# Lamp_Logic_Board_10.net
KiCad netlist of a schematic drawn in EAGLE
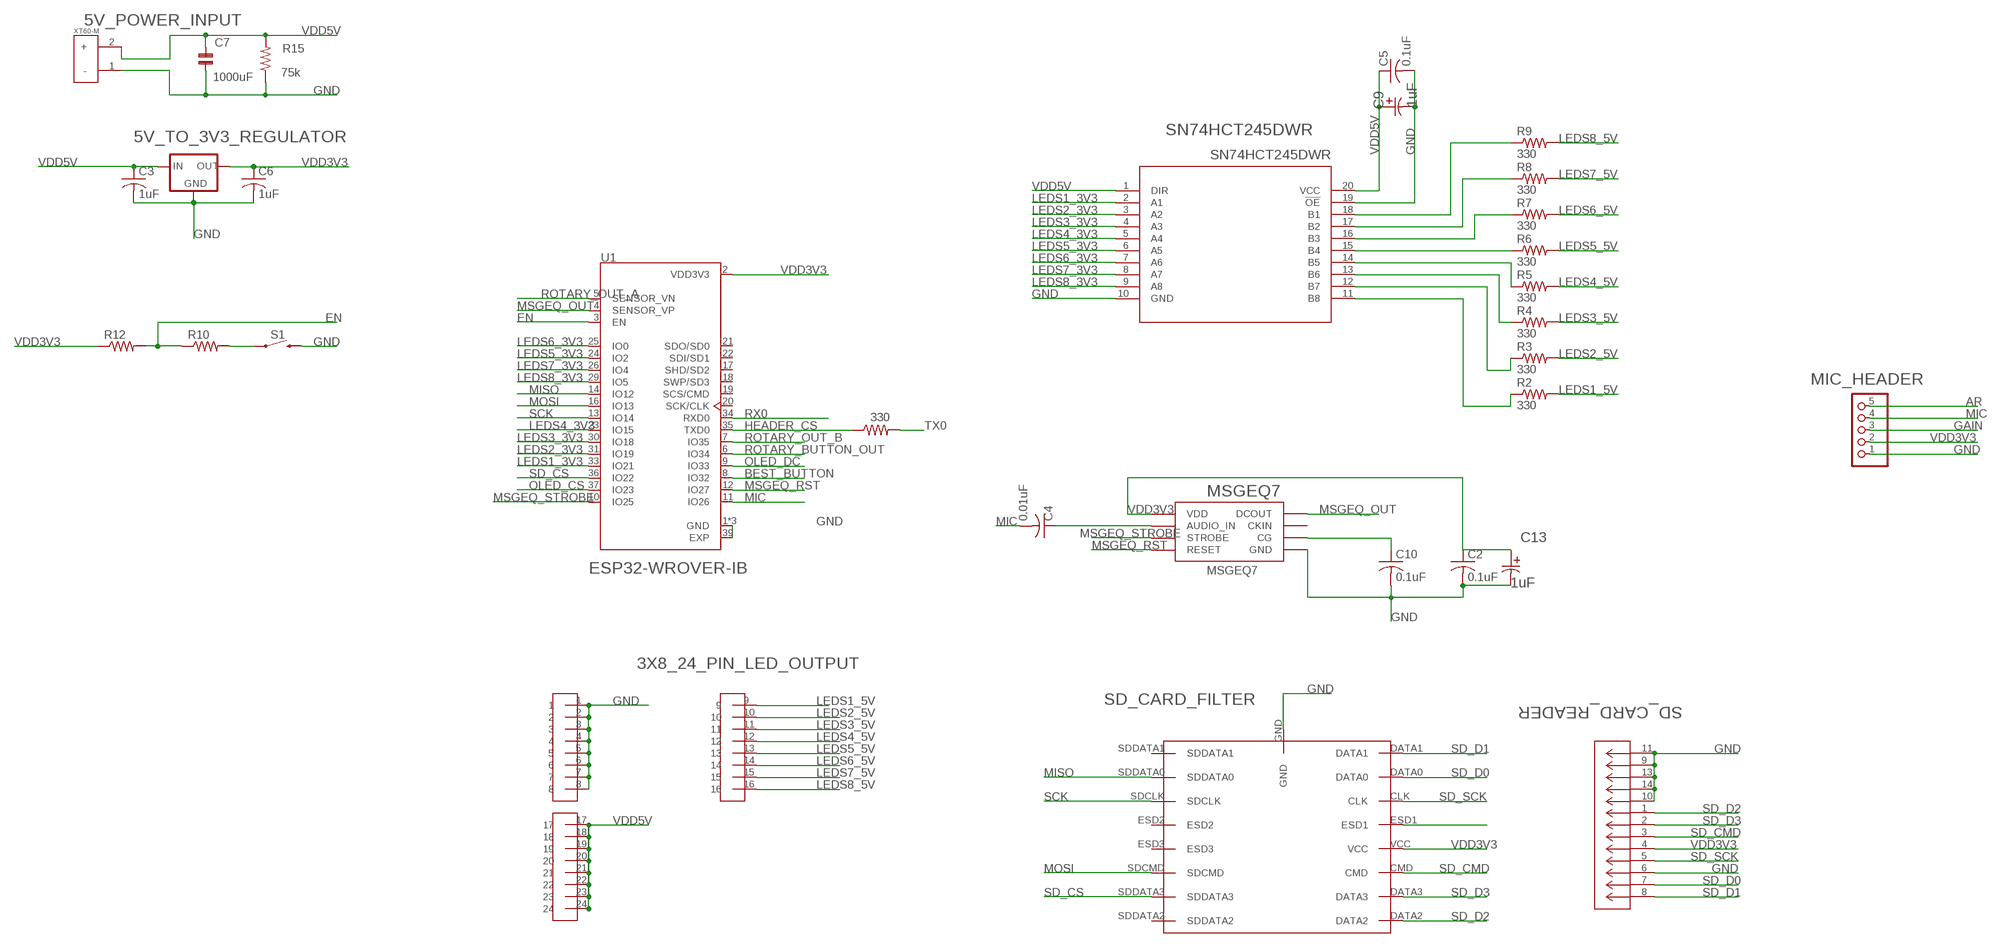
[diagram p0: schematic, sheet 1]

(export (version "E")
  (design (tool "Eeschema 10.0.6"))
  (components
    (comp (ref "3X8_24_PIN_LED_OUTPUT")
      (value "3X8PINHEAD")
      (footprint "eagle-import:3X8PINHEAD")
      (libsource (lib "eagle-import") (part "3X8PINHEAD"))
    )
    (comp (ref "5V_POWER_INPUT")
      (value "XT60-M")
      (footprint "eagle-import:AMASS_XT60-M")
      (fields (field (name "MF") "AMASS"))
      (libsource (lib "eagle-import") (part "XT60-M"))
    )
    (comp (ref "5V_TO_3V3_REGULATOR")
      (value "LM1117MP-1.8")
      (footprint "eagle-import:SOT223")
      (fields (field (name "MF") "Texas Instruments"))
      (libsource (lib "eagle-import") (part "LM1117?-MP1.8"))
    )
    (comp (ref "C2")
      (value "0.1uF")
      (footprint "eagle-import:C0805")
      (libsource (lib "eagle-import") (part "C-USC0805"))
    )
    (comp (ref "C3")
      (value "1uF")
      (footprint "eagle-import:C0402")
      (libsource (lib "eagle-import") (part "C-USC0402"))
    )
    (comp (ref "C4")
      (value "0.01uF")
      (footprint "eagle-import:C0402")
      (libsource (lib "eagle-import") (part "C-USC0402"))
    )
    (comp (ref "C5")
      (value "0.1uF")
      (footprint "eagle-import:C0805")
      (libsource (lib "eagle-import") (part "C-USC0805"))
    )
    (comp (ref "C6")
      (value "1uF")
      (footprint "eagle-import:C0402")
      (libsource (lib "eagle-import") (part "C-USC0402"))
    )
    (comp (ref "C7")
      (value "1000uF")
      (footprint "eagle-import:ENP2,0-5")
      (libsource (lib "eagle-import") (part "C-BP-2,0X5"))
    )
    (comp (ref "C9")
      (value "1uF")
      (footprint "eagle-import:CAP_EEFC_B")
      (fields (field (name "MANUFACTURER_PART_NUMBER") "EEEFC1V1R0R"))
      (libsource (lib "eagle-import") (part "EEEFC1V1R0R"))
    )
    (comp (ref "C10")
      (value "0.1uF")
      (footprint "eagle-import:C0805")
      (libsource (lib "eagle-import") (part "C-USC0805"))
    )
    (comp (ref "C13")
      (value "1uF")
      (footprint "eagle-import:CAP_EEFC_B")
      (fields (field (name "MANUFACTURER_PART_NUMBER") "EEEFC1V1R0R"))
      (libsource (lib "eagle-import") (part "EEEFC1V1R0R"))
    )
    (comp (ref "MIC_HEADER")
      (value "PINHD-1X5")
      (footprint "eagle-import:1X05")
      (libsource (lib "eagle-import") (part "PINHD-1X5"))
    )
    (comp (ref "MSGEQ7")
      (value "MSGEQ7DIL")
      (footprint "eagle-import:DIL-08")
      (fields
        (field (name "DIGI-KEY_PART_NUMBER") "1568-1544-ND")
        (field (name "MF") "SparkFun Electronics")
        (field (name "MP") "MSGEQ7")
      )
      (libsource (lib "eagle-import") (part "MSGEQ7DIL"))
    )
    (comp (ref "R1")
      (value "330")
      (footprint "eagle-import:R1206")
      (libsource (lib "eagle-import") (part "R-US_R1206"))
    )
    (comp (ref "R2")
      (value "330")
      (footprint "eagle-import:R1206")
      (libsource (lib "eagle-import") (part "R-US_R1206"))
    )
    (comp (ref "R3")
      (value "330")
      (footprint "eagle-import:R1206")
      (libsource (lib "eagle-import") (part "R-US_R1206"))
    )
    (comp (ref "R4")
      (value "330")
      (footprint "eagle-import:R1206")
      (libsource (lib "eagle-import") (part "R-US_R1206"))
    )
    (comp (ref "R5")
      (value "330")
      (footprint "eagle-import:R1206")
      (libsource (lib "eagle-import") (part "R-US_R1206"))
    )
    (comp (ref "R6")
      (value "330")
      (footprint "eagle-import:R1206")
      (libsource (lib "eagle-import") (part "R-US_R1206"))
    )
    (comp (ref "R7")
      (value "330")
      (footprint "eagle-import:R1206")
      (libsource (lib "eagle-import") (part "R-US_R1206"))
    )
    (comp (ref "R8")
      (value "330")
      (footprint "eagle-import:R1206")
      (libsource (lib "eagle-import") (part "R-US_R1206"))
    )
    (comp (ref "R9")
      (value "330")
      (footprint "eagle-import:R1206")
      (libsource (lib "eagle-import") (part "R-US_R1206"))
    )
    (comp (ref "R10")
      (value "330")
      (footprint "eagle-import:R1206")
      (libsource (lib "eagle-import") (part "R-US_R1206"))
    )
    (comp (ref "R12")
      (value "12k")
      (footprint "eagle-import:R0603")
      (libsource (lib "eagle-import") (part "R-US_R0603"))
    )
    (comp (ref "R15")
      (value "75k")
      (footprint "eagle-import:0309_12")
      (libsource (lib "eagle-import") (part "R-US_0309/12"))
    )
    (comp (ref "S1")
      (value "MOMENTARY-SWITCH-SPST-SMD-6.0X3.5MM")
      (footprint "eagle-import:TACTILE_SWITCH_SMD_6.0X3.5MM")
      (libsource (lib "eagle-import") (part "MOMENTARY-SWITCH-SPST-SMD-6.0X3.5MM"))
    )
    (comp (ref "SD_CARD_FILTER")
      (value "CM1624-08DE")
      (footprint "eagle-import:CM1624-08DE")
      (libsource (lib "eagle-import") (part "CM1624-08DE"))
    )
    (comp (ref "SD_CARD_READER")
      (value "LLC")
      (footprint "eagle-import:CON00218_8")
      (libsource (lib "eagle-import") (part "LLC"))
    )
    (comp (ref "SN74HCT245DWR")
      (value "SN74HCT245DWR")
      (footprint "eagle-import:DW20")
      (libsource (lib "eagle-import") (part "SN74HCT245DWR"))
    )
    (comp (ref "U1")
      (value "ESP32-WROVER-IB")
      (footprint "eagle-import:XCVR_ESP32-WROVER-I")
      (fields (field (name "MF") "Espressif Systems") (field (name "MP") "ESP32-WROVER-I"))
      (libsource (lib "eagle-import") (part "ESP32-WROVER-I"))
    )
  )
  (nets
    (net (code "1") (name "AR") (class "Default")
      (node (ref "MIC_HEADER") (pin "5") (pinfunction "5_5") (pintype "passive"))
    )
    (net (code "2") (name "BEST_BUTTON") (class "Default")
      (node (ref "U1") (pin "8") (pinfunction "IO32_8") (pintype "bidirectional"))
    )
    (net (code "3") (name "EN") (class "Default")
      (node (ref "R10") (pin "1") (pinfunction "1_1") (pintype "passive"))
      (node (ref "R12") (pin "2") (pinfunction "2_2") (pintype "passive"))
      (node (ref "U1") (pin "3") (pinfunction "EN_3") (pintype "input"))
    )
    (net (code "4") (name "GAIN") (class "Default")
      (node (ref "MIC_HEADER") (pin "3") (pinfunction "3_3") (pintype "passive"))
    )
    (net (code "5") (name "GND") (class "Default")
      (node (ref "3X8_24_PIN_LED_OUTPUT") (pin "1") (pinfunction "1_1") (pintype "bidirectional"))
      (node (ref "3X8_24_PIN_LED_OUTPUT") (pin "2") (pinfunction "2_2") (pintype "bidirectional"))
      (node (ref "3X8_24_PIN_LED_OUTPUT") (pin "3") (pinfunction "3_3") (pintype "bidirectional"))
      (node (ref "3X8_24_PIN_LED_OUTPUT") (pin "4") (pinfunction "4_4") (pintype "bidirectional"))
      (node (ref "3X8_24_PIN_LED_OUTPUT") (pin "5") (pinfunction "5_5") (pintype "bidirectional"))
      (node (ref "3X8_24_PIN_LED_OUTPUT") (pin "6") (pinfunction "6_6") (pintype "bidirectional"))
      (node (ref "3X8_24_PIN_LED_OUTPUT") (pin "7") (pinfunction "7_7") (pintype "bidirectional"))
      (node (ref "3X8_24_PIN_LED_OUTPUT") (pin "8") (pinfunction "8_8") (pintype "bidirectional"))
      (node (ref "5V_POWER_INPUT") (pin "1") (pinfunction "-_1") (pintype "passive"))
      (node (ref "5V_TO_3V3_REGULATOR") (pin "1") (pinfunction "GND_1") (pintype "input"))
      (node (ref "C10") (pin "2") (pinfunction "2_2") (pintype "passive"))
      (node (ref "C13") (pin "2") (pinfunction "2_2") (pintype "passive"))
      (node (ref "C2") (pin "2") (pinfunction "2_2") (pintype "passive"))
      (node (ref "C3") (pin "2") (pinfunction "2_2") (pintype "passive"))
      (node (ref "C5") (pin "2") (pinfunction "2_2") (pintype "passive"))
      (node (ref "C6") (pin "2") (pinfunction "2_2") (pintype "passive"))
      (node (ref "C7") (pin "1") (pinfunction "1_1") (pintype "passive"))
      (node (ref "C9") (pin "2") (pinfunction "2_2") (pintype "passive"))
      (node (ref "MIC_HEADER") (pin "1") (pinfunction "1_1") (pintype "passive"))
      (node (ref "MSGEQ7") (pin "2") (pinfunction "GND_2") (pintype "bidirectional"))
      (node (ref "R15") (pin "1") (pinfunction "1_1") (pintype "passive"))
      (node (ref "S1") (pin "2") (pinfunction "2_2") (pintype "passive"))
      (node (ref "SD_CARD_FILTER") (pin "GND") (pinfunction "GND_GND") (pintype "bidirectional"))
      (node (ref "SD_CARD_READER") (pin "10") (pinfunction "10_10") (pintype "passive"))
      (node (ref "SD_CARD_READER") (pin "11") (pinfunction "11_11") (pintype "passive"))
      (node (ref "SD_CARD_READER") (pin "13") (pinfunction "13_13") (pintype "passive"))
      (node (ref "SD_CARD_READER") (pin "14") (pinfunction "14_14") (pintype "passive"))
      (node (ref "SD_CARD_READER") (pin "6") (pinfunction "6_6") (pintype "passive"))
      (node (ref "SD_CARD_READER") (pin "9") (pinfunction "9_9") (pintype "passive"))
      (node (ref "SN74HCT245DWR") (pin "10") (pinfunction "GND_10") (pintype "power_in"))
      (node (ref "SN74HCT245DWR") (pin "19") (pinfunction "~{OE}_19") (pintype "input"))
      (node (ref "U1") (pin "1") (pinfunction "GND_1") (pintype "power_in"))
      (node (ref "U1") (pin "15") (pinfunction "GND_15") (pintype "power_in"))
      (node (ref "U1") (pin "38") (pinfunction "GND_38") (pintype "power_in"))
      (node (ref "U1") (pin "39") (pinfunction "EXP_39") (pintype "power_in"))
    )
    (net (code "6") (name "HEADER_CS") (class "Default")
      (node (ref "R1") (pin "1") (pinfunction "1_1") (pintype "passive"))
      (node (ref "U1") (pin "35") (pinfunction "TXD0_35") (pintype "bidirectional"))
    )
    (net (code "7") (name "LEDS1_3V3") (class "Default")
      (node (ref "SN74HCT245DWR") (pin "2") (pinfunction "A1_2") (pintype "bidirectional"))
      (node (ref "U1") (pin "33") (pinfunction "IO21_33") (pintype "bidirectional"))
    )
    (net (code "8") (name "LEDS1_5V") (class "Default")
      (node (ref "3X8_24_PIN_LED_OUTPUT") (pin "9") (pinfunction "9_9") (pintype "bidirectional"))
      (node (ref "R2") (pin "2") (pinfunction "2_2") (pintype "passive"))
    )
    (net (code "9") (name "LEDS2_3V3") (class "Default")
      (node (ref "SN74HCT245DWR") (pin "3") (pinfunction "A2_3") (pintype "bidirectional"))
      (node (ref "U1") (pin "31") (pinfunction "IO19_31") (pintype "bidirectional"))
    )
    (net (code "10") (name "LEDS2_5V") (class "Default")
      (node (ref "3X8_24_PIN_LED_OUTPUT") (pin "10") (pinfunction "10_10") (pintype "bidirectional"))
      (node (ref "R3") (pin "2") (pinfunction "2_2") (pintype "passive"))
    )
    (net (code "11") (name "LEDS3_3V3") (class "Default")
      (node (ref "SN74HCT245DWR") (pin "4") (pinfunction "A3_4") (pintype "bidirectional"))
      (node (ref "U1") (pin "30") (pinfunction "IO18_30") (pintype "bidirectional"))
    )
    (net (code "12") (name "LEDS3_5V") (class "Default")
      (node (ref "3X8_24_PIN_LED_OUTPUT") (pin "11") (pinfunction "11_11") (pintype "bidirectional"))
      (node (ref "R4") (pin "2") (pinfunction "2_2") (pintype "passive"))
    )
    (net (code "13") (name "LEDS4_3V3") (class "Default")
      (node (ref "SN74HCT245DWR") (pin "5") (pinfunction "A4_5") (pintype "bidirectional"))
      (node (ref "U1") (pin "23") (pinfunction "IO15_23") (pintype "bidirectional"))
    )
    (net (code "14") (name "LEDS4_5V") (class "Default")
      (node (ref "3X8_24_PIN_LED_OUTPUT") (pin "12") (pinfunction "12_12") (pintype "bidirectional"))
      (node (ref "R5") (pin "2") (pinfunction "2_2") (pintype "passive"))
    )
    (net (code "15") (name "LEDS5_3V3") (class "Default")
      (node (ref "SN74HCT245DWR") (pin "6") (pinfunction "A5_6") (pintype "bidirectional"))
      (node (ref "U1") (pin "24") (pinfunction "IO2_24") (pintype "bidirectional"))
    )
    (net (code "16") (name "LEDS5_5V") (class "Default")
      (node (ref "3X8_24_PIN_LED_OUTPUT") (pin "13") (pinfunction "13_13") (pintype "bidirectional"))
      (node (ref "R6") (pin "2") (pinfunction "2_2") (pintype "passive"))
    )
    (net (code "17") (name "LEDS6_3V3") (class "Default")
      (node (ref "SN74HCT245DWR") (pin "7") (pinfunction "A6_7") (pintype "bidirectional"))
      (node (ref "U1") (pin "25") (pinfunction "IO0_25") (pintype "bidirectional"))
    )
    (net (code "18") (name "LEDS6_5V") (class "Default")
      (node (ref "3X8_24_PIN_LED_OUTPUT") (pin "14") (pinfunction "14_14") (pintype "bidirectional"))
      (node (ref "R7") (pin "2") (pinfunction "2_2") (pintype "passive"))
    )
    (net (code "19") (name "LEDS7_3V3") (class "Default")
      (node (ref "SN74HCT245DWR") (pin "8") (pinfunction "A7_8") (pintype "bidirectional"))
      (node (ref "U1") (pin "26") (pinfunction "IO4_26") (pintype "bidirectional"))
    )
    (net (code "20") (name "LEDS7_5V") (class "Default")
      (node (ref "3X8_24_PIN_LED_OUTPUT") (pin "15") (pinfunction "15_15") (pintype "bidirectional"))
      (node (ref "R8") (pin "2") (pinfunction "2_2") (pintype "passive"))
    )
    (net (code "21") (name "LEDS8_3V3") (class "Default")
      (node (ref "SN74HCT245DWR") (pin "9") (pinfunction "A8_9") (pintype "bidirectional"))
      (node (ref "U1") (pin "29") (pinfunction "IO5_29") (pintype "bidirectional"))
    )
    (net (code "22") (name "LEDS8_5V") (class "Default")
      (node (ref "3X8_24_PIN_LED_OUTPUT") (pin "16") (pinfunction "16_16") (pintype "bidirectional"))
      (node (ref "R9") (pin "2") (pinfunction "2_2") (pintype "passive"))
    )
    (net (code "23") (name "MIC") (class "Default")
      (node (ref "C4") (pin "2") (pinfunction "2_2") (pintype "passive"))
      (node (ref "MIC_HEADER") (pin "4") (pinfunction "4_4") (pintype "passive"))
      (node (ref "U1") (pin "11") (pinfunction "IO26_11") (pintype "bidirectional"))
    )
    (net (code "24") (name "MISO") (class "Default")
      (node (ref "SD_CARD_FILTER") (pin "SDDATA0") (pinfunction "SDDATA0_SDDATA0") (pintype "bidirectional"))
      (node (ref "U1") (pin "14") (pinfunction "IO12_14") (pintype "bidirectional"))
    )
    (net (code "25") (name "MOSI") (class "Default")
      (node (ref "SD_CARD_FILTER") (pin "SDCMD") (pinfunction "SDCMD_SDCMD") (pintype "bidirectional"))
      (node (ref "U1") (pin "16") (pinfunction "IO13_16") (pintype "bidirectional"))
    )
    (net (code "26") (name "MSGEQ_OUT") (class "Default")
      (node (ref "MSGEQ7") (pin "3") (pinfunction "DCOUT_3") (pintype "bidirectional"))
      (node (ref "U1") (pin "4") (pinfunction "SENSOR_VP_4") (pintype "input"))
    )
    (net (code "27") (name "MSGEQ_RST") (class "Default")
      (node (ref "MSGEQ7") (pin "7") (pinfunction "RESET_7") (pintype "input"))
      (node (ref "U1") (pin "12") (pinfunction "IO27_12") (pintype "bidirectional"))
    )
    (net (code "28") (name "MSGEQ_STROBE") (class "Default")
      (node (ref "MSGEQ7") (pin "4") (pinfunction "STROBE_4") (pintype "input"))
      (node (ref "U1") (pin "10") (pinfunction "IO25_10") (pintype "bidirectional"))
    )
    (net (code "29") (name "Net-(MSGEQ7-AUDIO_IN)") (class "Default")
      (node (ref "C4") (pin "1") (pinfunction "1_1") (pintype "passive"))
      (node (ref "MSGEQ7") (pin "5") (pinfunction "AUDIO_IN_5") (pintype "input"))
    )
    (net (code "30") (name "Net-(MSGEQ7-CG)") (class "Default")
      (node (ref "C10") (pin "1") (pinfunction "1_1") (pintype "passive"))
      (node (ref "MSGEQ7") (pin "6") (pinfunction "CG_6") (pintype "bidirectional"))
    )
    (net (code "31") (name "Net-(R10-Pad2)") (class "Default")
      (node (ref "R10") (pin "2") (pinfunction "2_2") (pintype "passive"))
      (node (ref "S1") (pin "1") (pinfunction "1_1") (pintype "passive"))
    )
    (net (code "32") (name "Net-(SN74HCT245DWR-B1)") (class "Default")
      (node (ref "R9") (pin "1") (pinfunction "1_1") (pintype "passive"))
      (node (ref "SN74HCT245DWR") (pin "18") (pinfunction "B1_18") (pintype "bidirectional"))
    )
    (net (code "33") (name "Net-(SN74HCT245DWR-B2)") (class "Default")
      (node (ref "R8") (pin "1") (pinfunction "1_1") (pintype "passive"))
      (node (ref "SN74HCT245DWR") (pin "17") (pinfunction "B2_17") (pintype "bidirectional"))
    )
    (net (code "34") (name "Net-(SN74HCT245DWR-B3)") (class "Default")
      (node (ref "R7") (pin "1") (pinfunction "1_1") (pintype "passive"))
      (node (ref "SN74HCT245DWR") (pin "16") (pinfunction "B3_16") (pintype "bidirectional"))
    )
    (net (code "35") (name "Net-(SN74HCT245DWR-B4)") (class "Default")
      (node (ref "R6") (pin "1") (pinfunction "1_1") (pintype "passive"))
      (node (ref "SN74HCT245DWR") (pin "15") (pinfunction "B4_15") (pintype "bidirectional"))
    )
    (net (code "36") (name "Net-(SN74HCT245DWR-B5)") (class "Default")
      (node (ref "R5") (pin "1") (pinfunction "1_1") (pintype "passive"))
      (node (ref "SN74HCT245DWR") (pin "14") (pinfunction "B5_14") (pintype "bidirectional"))
    )
    (net (code "37") (name "Net-(SN74HCT245DWR-B6)") (class "Default")
      (node (ref "R4") (pin "1") (pinfunction "1_1") (pintype "passive"))
      (node (ref "SN74HCT245DWR") (pin "13") (pinfunction "B6_13") (pintype "bidirectional"))
    )
    (net (code "38") (name "Net-(SN74HCT245DWR-B7)") (class "Default")
      (node (ref "R3") (pin "1") (pinfunction "1_1") (pintype "passive"))
      (node (ref "SN74HCT245DWR") (pin "12") (pinfunction "B7_12") (pintype "bidirectional"))
    )
    (net (code "39") (name "Net-(SN74HCT245DWR-B8)") (class "Default")
      (node (ref "R2") (pin "1") (pinfunction "1_1") (pintype "passive"))
      (node (ref "SN74HCT245DWR") (pin "11") (pinfunction "B8_11") (pintype "bidirectional"))
    )
    (net (code "40") (name "OLED_CS") (class "Default")
      (node (ref "U1") (pin "37") (pinfunction "IO23_37") (pintype "bidirectional"))
    )
    (net (code "41") (name "OLED_DC") (class "Default")
      (node (ref "U1") (pin "9") (pinfunction "IO33_9") (pintype "bidirectional"))
    )
    (net (code "42") (name "ROTARY_BUTTON_OUT") (class "Default")
      (node (ref "U1") (pin "6") (pinfunction "IO34_6") (pintype "input"))
    )
    (net (code "43") (name "ROTARY_OUT_A") (class "Default")
      (node (ref "U1") (pin "5") (pinfunction "SENSOR_VN_5") (pintype "input"))
    )
    (net (code "44") (name "ROTARY_OUT_B") (class "Default")
      (node (ref "U1") (pin "7") (pinfunction "IO35_7") (pintype "input"))
    )
    (net (code "45") (name "RX0") (class "Default")
      (node (ref "U1") (pin "34") (pinfunction "RXD0_34") (pintype "bidirectional"))
    )
    (net (code "46") (name "SCK") (class "Default")
      (node (ref "SD_CARD_FILTER") (pin "SDCLK") (pinfunction "SDCLK_SDCLK") (pintype "bidirectional"))
      (node (ref "U1") (pin "13") (pinfunction "IO14_13") (pintype "bidirectional"))
    )
    (net (code "47") (name "SD_CMD") (class "Default")
      (node (ref "SD_CARD_FILTER") (pin "CMD") (pinfunction "CMD_CMD") (pintype "bidirectional"))
      (node (ref "SD_CARD_READER") (pin "3") (pinfunction "3_3") (pintype "passive"))
    )
    (net (code "48") (name "SD_CS") (class "Default")
      (node (ref "SD_CARD_FILTER") (pin "SDDATA3") (pinfunction "SDDATA3_SDDATA3") (pintype "bidirectional"))
      (node (ref "U1") (pin "36") (pinfunction "IO22_36") (pintype "bidirectional"))
    )
    (net (code "49") (name "SD_D0") (class "Default")
      (node (ref "SD_CARD_FILTER") (pin "DATA0") (pinfunction "DATA0_DATA0") (pintype "bidirectional"))
      (node (ref "SD_CARD_READER") (pin "7") (pinfunction "7_7") (pintype "passive"))
    )
    (net (code "50") (name "SD_D1") (class "Default")
      (node (ref "SD_CARD_FILTER") (pin "DATA1") (pinfunction "DATA1_DATA1") (pintype "bidirectional"))
      (node (ref "SD_CARD_READER") (pin "8") (pinfunction "8_8") (pintype "passive"))
    )
    (net (code "51") (name "SD_D2") (class "Default")
      (node (ref "SD_CARD_FILTER") (pin "DATA2") (pinfunction "DATA2_DATA2") (pintype "bidirectional"))
      (node (ref "SD_CARD_READER") (pin "1") (pinfunction "1_1") (pintype "passive"))
    )
    (net (code "52") (name "SD_D3") (class "Default")
      (node (ref "SD_CARD_FILTER") (pin "DATA3") (pinfunction "DATA3_DATA3") (pintype "bidirectional"))
      (node (ref "SD_CARD_READER") (pin "2") (pinfunction "2_2") (pintype "passive"))
    )
    (net (code "53") (name "SD_SCK") (class "Default")
      (node (ref "SD_CARD_FILTER") (pin "CLK") (pinfunction "CLK_CLK") (pintype "bidirectional"))
      (node (ref "SD_CARD_READER") (pin "5") (pinfunction "5_5") (pintype "passive"))
    )
    (net (code "54") (name "TX0") (class "Default")
      (node (ref "R1") (pin "2") (pinfunction "2_2") (pintype "passive"))
    )
    (net (code "55") (name "VDD3V3") (class "Default")
      (node (ref "5V_TO_3V3_REGULATOR") (pin "2") (pinfunction "OUT_2") (pintype "passive"))
      (node (ref "5V_TO_3V3_REGULATOR") (pin "4") (pinfunction "OUT_4") (pintype "passive"))
      (node (ref "C13") (pin "1") (pinfunction "1_1") (pintype "passive"))
      (node (ref "C2") (pin "1") (pinfunction "1_1") (pintype "passive"))
      (node (ref "C6") (pin "1") (pinfunction "1_1") (pintype "passive"))
      (node (ref "MIC_HEADER") (pin "2") (pinfunction "2_2") (pintype "passive"))
      (node (ref "MSGEQ7") (pin "1") (pinfunction "VDD_1") (pintype "input"))
      (node (ref "R12") (pin "1") (pinfunction "1_1") (pintype "passive"))
      (node (ref "SD_CARD_FILTER") (pin "VCC") (pinfunction "VCC_VCC") (pintype "bidirectional"))
      (node (ref "SD_CARD_READER") (pin "4") (pinfunction "4_4") (pintype "passive"))
      (node (ref "U1") (pin "2") (pinfunction "VDD3V3_2") (pintype "power_in"))
    )
    (net (code "56") (name "VDD5V") (class "Default")
      (node (ref "3X8_24_PIN_LED_OUTPUT") (pin "17") (pinfunction "17_17") (pintype "bidirectional"))
      (node (ref "3X8_24_PIN_LED_OUTPUT") (pin "18") (pinfunction "18_18") (pintype "bidirectional"))
      (node (ref "3X8_24_PIN_LED_OUTPUT") (pin "19") (pinfunction "19_19") (pintype "bidirectional"))
      (node (ref "3X8_24_PIN_LED_OUTPUT") (pin "20") (pinfunction "20_20") (pintype "bidirectional"))
      (node (ref "3X8_24_PIN_LED_OUTPUT") (pin "21") (pinfunction "21_21") (pintype "bidirectional"))
      (node (ref "3X8_24_PIN_LED_OUTPUT") (pin "22") (pinfunction "22_22") (pintype "bidirectional"))
      (node (ref "3X8_24_PIN_LED_OUTPUT") (pin "23") (pinfunction "23_23") (pintype "bidirectional"))
      (node (ref "3X8_24_PIN_LED_OUTPUT") (pin "24") (pinfunction "24_24") (pintype "bidirectional"))
      (node (ref "5V_POWER_INPUT") (pin "2") (pinfunction "+_2") (pintype "passive"))
      (node (ref "5V_TO_3V3_REGULATOR") (pin "3") (pinfunction "IN_3") (pintype "input"))
      (node (ref "C3") (pin "1") (pinfunction "1_1") (pintype "passive"))
      (node (ref "C5") (pin "1") (pinfunction "1_1") (pintype "passive"))
      (node (ref "C7") (pin "2") (pinfunction "2_2") (pintype "passive"))
      (node (ref "C9") (pin "1") (pinfunction "1_1") (pintype "passive"))
      (node (ref "R15") (pin "2") (pinfunction "2_2") (pintype "passive"))
      (node (ref "SN74HCT245DWR") (pin "1") (pinfunction "DIR_1") (pintype "input"))
      (node (ref "SN74HCT245DWR") (pin "20") (pinfunction "VCC_20") (pintype "power_in"))
    )
    (net (code "57") (name "unconnected-(MSGEQ7-CKIN-Pad8)") (class "Default")
      (node (ref "MSGEQ7") (pin "8") (pinfunction "CKIN_8") (pintype "bidirectional"))
    )
    (net (code "58") (name "unconnected-(SD_CARD_FILTER-PadESD1)") (class "Default")
      (node (ref "SD_CARD_FILTER") (pin "ESD1") (pinfunction "ESD1_ESD1") (pintype "bidirectional"))
    )
    (net (code "59") (name "unconnected-(SD_CARD_FILTER-PadESD2)") (class "Default")
      (node (ref "SD_CARD_FILTER") (pin "ESD2") (pinfunction "ESD2_ESD2") (pintype "bidirectional"))
    )
    (net (code "60") (name "unconnected-(SD_CARD_FILTER-PadESD3)") (class "Default")
      (node (ref "SD_CARD_FILTER") (pin "ESD3") (pinfunction "ESD3_ESD3") (pintype "bidirectional"))
    )
    (net (code "61") (name "unconnected-(SD_CARD_FILTER-PadSDDATA1)") (class "Default")
      (node (ref "SD_CARD_FILTER") (pin "SDDATA1") (pinfunction "SDDATA1_SDDATA1") (pintype "bidirectional"))
    )
    (net (code "62") (name "unconnected-(SD_CARD_FILTER-PadSDDATA2)") (class "Default")
      (node (ref "SD_CARD_FILTER") (pin "SDDATA2") (pinfunction "SDDATA2_SDDATA2") (pintype "bidirectional"))
    )
    (net (code "63") (name "unconnected-(U1-SCK{slash}CLK-Pad20)") (class "Default")
      (node (ref "U1") (pin "20") (pinfunction "SCK/CLK_20") (pintype "bidirectional"))
    )
    (net (code "64") (name "unconnected-(U1-SCS{slash}CMD-Pad19)") (class "Default")
      (node (ref "U1") (pin "19") (pinfunction "SCS/CMD_19") (pintype "bidirectional"))
    )
    (net (code "65") (name "unconnected-(U1-SDI{slash}SD1-Pad22)") (class "Default")
      (node (ref "U1") (pin "22") (pinfunction "SDI/SD1_22") (pintype "bidirectional"))
    )
    (net (code "66") (name "unconnected-(U1-SDO{slash}SD0-Pad21)") (class "Default")
      (node (ref "U1") (pin "21") (pinfunction "SDO/SD0_21") (pintype "bidirectional"))
    )
    (net (code "67") (name "unconnected-(U1-SHD{slash}SD2-Pad17)") (class "Default")
      (node (ref "U1") (pin "17") (pinfunction "SHD/SD2_17") (pintype "bidirectional"))
    )
    (net (code "68") (name "unconnected-(U1-SWP{slash}SD3-Pad18)") (class "Default")
      (node (ref "U1") (pin "18") (pinfunction "SWP/SD3_18") (pintype "bidirectional"))
    )
  )
)
